# 300w.net
KiCad netlist of a schematic drawn in EasyEDA Pro
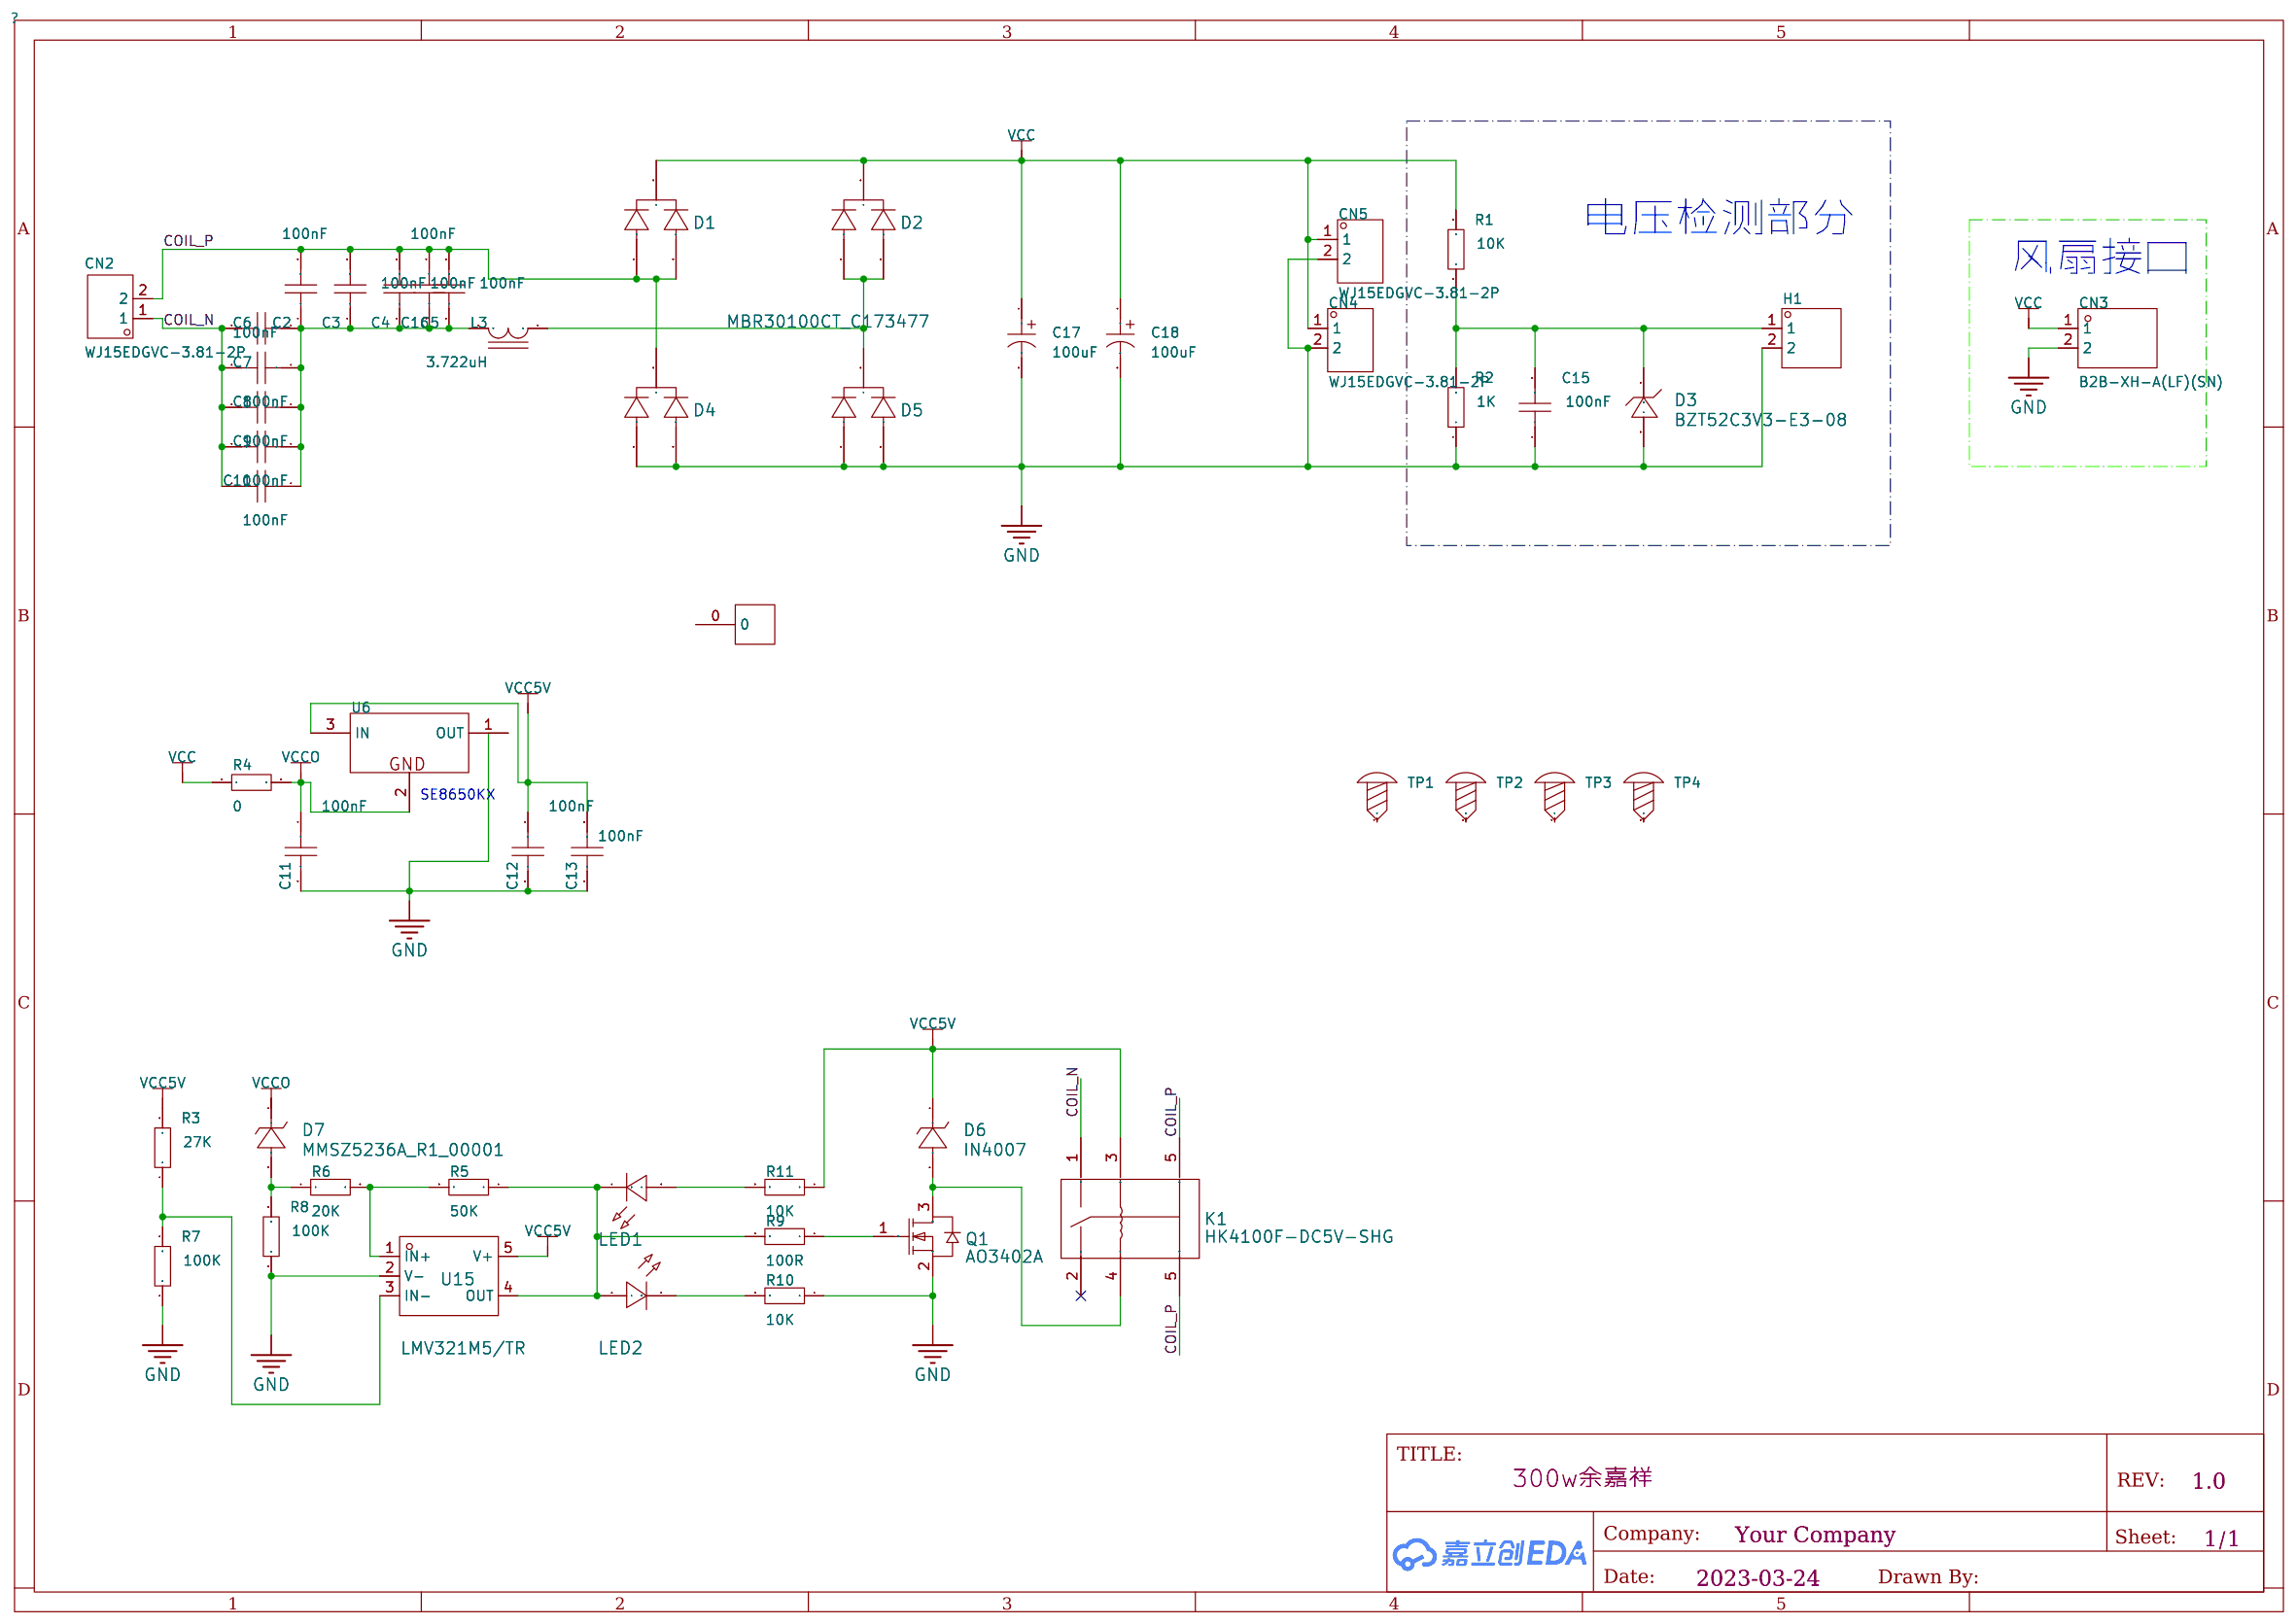
[diagram p0: schematic sheet]

(export (version "E")
  (design (tool "Eeschema 10.0.6"))
  (components
    (comp (ref "C2")
      (value "100nF")
      (footprint "easyedapro:C1206")
      (description "容值:100nF;精度:±10%;额定电压:50V;温度系数:X7R;")
      (libsource (lib "easyedapro") (part "C1210X7R475K630NT"))
    )
    (comp (ref "C3")
      (value "100nF")
      (footprint "easyedapro:C1206")
      (description "容值:100nF;精度:±10%;额定电压:50V;温度系数:X7R;")
      (libsource (lib "easyedapro") (part "C1210X7R475K630NT"))
    )
    (comp (ref "C4")
      (value "100nF")
      (footprint "easyedapro:C1206")
      (description "容值:100nF;精度:±10%;额定电压:50V;温度系数:X7R;")
      (libsource (lib "easyedapro") (part "C1210X7R475K630NT"))
    )
    (comp (ref "C5")
      (value "100nF")
      (footprint "easyedapro:C1206")
      (description "容值:100nF;精度:±10%;额定电压:50V;温度系数:X7R;")
      (libsource (lib "easyedapro") (part "C1210X7R475K630NT"))
    )
    (comp (ref "C6")
      (value "100nF")
      (footprint "easyedapro:C1206")
      (description "容值:100nF;精度:±10%;额定电压:50V;温度系数:X7R;")
      (libsource (lib "easyedapro") (part "C1210X7R475K630NT"))
    )
    (comp (ref "C7")
      (value "100nF")
      (footprint "easyedapro:C1206")
      (description "容值:100nF;精度:±10%;额定电压:50V;温度系数:X7R;")
      (libsource (lib "easyedapro") (part "C1210X7R475K630NT"))
    )
    (comp (ref "C8")
      (value "100nF")
      (footprint "easyedapro:C1206")
      (description "容值:100nF;精度:±10%;额定电压:50V;温度系数:X7R;")
      (libsource (lib "easyedapro") (part "C1210X7R475K630NT"))
    )
    (comp (ref "C9")
      (value "100nF")
      (footprint "easyedapro:C1206")
      (description "容值:100nF;精度:±10%;额定电压:50V;温度系数:X7R;")
      (libsource (lib "easyedapro") (part "C1210X7R475K630NT"))
    )
    (comp (ref "C10")
      (value "100nF")
      (footprint "easyedapro:C1206")
      (description "容值:100nF;精度:±10%;额定电压:50V;温度系数:X7R;")
      (libsource (lib "easyedapro") (part "C1210X7R475K630NT"))
    )
    (comp (ref "C11")
      (value "100nF")
      (footprint "easyedapro:C1206")
      (description "容值:100nF;精度:±10%;额定电压:50V;温度系数:X7R;")
      (libsource (lib "easyedapro") (part "C1210X7R475K630NT"))
    )
    (comp (ref "C12")
      (value "100nF")
      (footprint "easyedapro:C1206")
      (description "容值:100nF;精度:±10%;额定电压:50V;温度系数:X7R;")
      (libsource (lib "easyedapro") (part "C1210X7R475K630NT"))
    )
    (comp (ref "C13")
      (value "100nF")
      (footprint "easyedapro:C1206")
      (description "容值:100nF;精度:±10%;额定电压:50V;温度系数:X7R;")
      (libsource (lib "easyedapro") (part "C1210X7R475K630NT"))
    )
    (comp (ref "C15")
      (value "100nF")
      (footprint "easyedapro:C1206")
      (description "容值:100nF;精度:±10%;额定电压:50V;温度系数:X7R;")
      (libsource (lib "easyedapro") (part "C1210X7R475K630NT"))
    )
    (comp (ref "C16")
      (value "100nF")
      (footprint "easyedapro:C1206")
      (description "容值:100nF;精度:±10%;额定电压:50V;温度系数:X7R;")
      (libsource (lib "easyedapro") (part "C1210X7R475K630NT"))
    )
    (comp (ref "C17")
      (value "100uF")
      (footprint "easyedapro:CAP-TH_BD10.0-P5.00-D0.6-FD")
      (description "类型:-;容值:470uF;精度:±20%;额定电压:35V;纹波电流:-;等效串联电阻:-;")
      (fields
        (field (name "Manufacturer Part") "KNH2470UF35V149EC0017")
        (field (name "Manufacturer") "KNSCHA(科尼盛)")
      )
      (libsource (lib "easyedapro") (part "KNH2470UF35V149EC0017"))
    )
    (comp (ref "C18")
      (value "100uF")
      (footprint "easyedapro:CAP-TH_BD10.0-P5.00-D0.6-FD")
      (description "类型:-;容值:470uF;精度:±20%;额定电压:35V;纹波电流:-;等效串联电阻:-;")
      (fields
        (field (name "Manufacturer Part") "KNH2470UF35V149EC0017")
        (field (name "Manufacturer") "KNSCHA(科尼盛)")
      )
      (libsource (lib "easyedapro") (part "KNH2470UF35V149EC0017"))
    )
    (comp (ref "CN2")
      (value "WJ15EDGVC-3.81-2P")
      (footprint "easyedapro:CONN-TH_WJ15EDGVC-3.81-2P")
      (description "连接器类型:板端/插座-闭口;结构:1x2P;间距:3.81mm;排数:1;每排PIN数:2;安装方式:直针;颜色:绿色;")
      (fields (field (name "Manufacturer") "KANGNEX(康奈克斯电气)"))
      (libsource (lib "easyedapro") (part "WJ15EDGVC-3.81-2P"))
    )
    (comp (ref "CN3")
      (value "B2B-XH-A(LF)(SN)")
      (footprint "easyedapro:CONN-TH_B2B-XH-A-LF-SN")
      (description "参考系列:XH;间距:2.5mm;插针结构:1x2P;排数:1;每排PIN数:2;行距:-;安装方式:-;触头材质:黄铜;")
      (fields (field (name "Manufacturer") "JST"))
      (libsource (lib "easyedapro") (part "B2B-XH-A (LF)(SN)"))
    )
    (comp (ref "CN4")
      (value "WJ15EDGVC-3.81-2P")
      (footprint "easyedapro:CONN-TH_WJ15EDGVC-3.81-2P")
      (description "连接器类型:板端/插座-闭口;结构:1x2P;间距:3.81mm;排数:1;每排PIN数:2;安装方式:直针;颜色:绿色;")
      (fields (field (name "Manufacturer") "KANGNEX(康奈克斯电气)"))
      (libsource (lib "easyedapro") (part "WJ15EDGVC-3.81-2P"))
    )
    (comp (ref "CN5")
      (value "WJ15EDGVC-3.81-2P")
      (footprint "easyedapro:CONN-TH_WJ15EDGVC-3.81-2P")
      (description "连接器类型:板端/插座-闭口;结构:1x2P;间距:3.81mm;排数:1;每排PIN数:2;安装方式:直针;颜色:绿色;")
      (fields (field (name "Manufacturer") "KANGNEX(康奈克斯电气)"))
      (libsource (lib "easyedapro") (part "WJ15EDGVC-3.81-2P"))
    )
    (comp (ref "D1")
      (value "MBR30100CT")
      (footprint "easyedapro:TO-220AB-3_L10.3-W5.0-P2.54-L")
      (fields (field (name "Manufacturer") "MDD"))
      (libsource (lib "easyedapro") (part "MBR30100CT_C173477"))
    )
    (comp (ref "D2")
      (value "MBR30100CT")
      (footprint "easyedapro:TO-220AB-3_L10.3-W5.0-P2.54-L")
      (fields (field (name "Manufacturer") "MDD"))
      (libsource (lib "easyedapro") (part "MBR30100CT_C173477"))
    )
    (comp (ref "D3")
      (value "BZT52C3V3-E3-08")
      (footprint "easyedapro:SOD-123_L2.7-W1.6-LS3.7-RD")
      (fields (field (name "Manufacturer") "VISHAY(威世)"))
      (libsource (lib "easyedapro") (part "BZT52C3V3-E3-08"))
    )
    (comp (ref "D4")
      (value "MBR30100CT_C173477")
      (footprint "easyedapro:TO-220AB-3_L10.3-W5.0-P2.54-L")
      (fields (field (name "Manufacturer Part") "MBR30100CT") (field (name "Manufacturer") "MDD"))
      (libsource (lib "easyedapro") (part "MBR30100CT_C173477"))
    )
    (comp (ref "D5")
      (value "MBR30100CT")
      (footprint "easyedapro:TO-220AB-3_L10.3-W5.0-P2.54-L")
      (fields (field (name "Manufacturer") "MDD"))
      (libsource (lib "easyedapro") (part "MBR30100CT_C173477"))
    )
    (comp (ref "D6")
      (value "IN4007")
      (footprint "easyedapro:SOD-123F_L2.7-W1.6-LS3.8-RD-1")
      (fields
        (field (name "Manufacturer Part") "MMSZ5236A_R1_00001")
        (field (name "Manufacturer") "PANJIT(强茂)")
      )
      (libsource (lib "easyedapro") (part "MMSZ5236A_R1_00001"))
    )
    (comp (ref "D7")
      (value "MMSZ5236A_R1_00001")
      (footprint "easyedapro:SOD-123F_L2.7-W1.6-LS3.8-RD-1")
      (fields (field (name "Manufacturer") "PANJIT(强茂)"))
      (libsource (lib "easyedapro") (part "MMSZ5236A_R1_00001"))
    )
    (comp (ref "H1")
      (value "~")
      (footprint "easyedapro:HDR-TH_2P-P2.54-V-M-1")
      (libsource (lib "easyedapro") (part "210S-1*2P L=11.6MMGold-plated black"))
    )
    (comp (ref "K1")
      (value "HK4100F-DC5V-SHG")
      (footprint "easyedapro:RELAY-TH_HK4100F-DC5V-SHG")
      (fields (field (name "Manufacturer") "汇科"))
      (libsource (lib "easyedapro") (part "HK4100F-DC5V-SHG"))
    )
    (comp (ref "L3")
      (value "3.722uH")
      (footprint "easyedapro:T94/106-LAY")
      (libsource (lib "easyedapro") (part "Ind-Power_2"))
    )
    (comp (ref "LED1")
      (value "~")
      (footprint "easyedapro:LED0805-RD_RED")
      (libsource (lib "easyedapro") (part "LED_R"))
    )
    (comp (ref "LED2")
      (value "~")
      (footprint "easyedapro:LED0805-RD_RED")
      (libsource (lib "easyedapro") (part "LED_R"))
    )
    (comp (ref "Q1")
      (value "AO3402A")
      (footprint "easyedapro:SOT-23-3_L2.9-W1.3-P1.90-LS2.4-BR")
      (fields (field (name "Manufacturer") "UMW(广东友台半导体)"))
      (libsource (lib "easyedapro") (part "AO3402A"))
    )
    (comp (ref "R1") (value "10K") (footprint "easyedapro:R0603") (libsource (lib "easyedapro") (part "电阻")))
    (comp (ref "R2") (value "1K") (footprint "easyedapro:R0603") (libsource (lib "easyedapro") (part "电阻")))
    (comp (ref "R3") (value "27K") (footprint "easyedapro:R0603") (libsource (lib "easyedapro") (part "电阻")))
    (comp (ref "R4") (value "0") (footprint "easyedapro:R0603") (libsource (lib "easyedapro") (part "电阻")))
    (comp (ref "R5") (value "50K") (footprint "easyedapro:R0603") (libsource (lib "easyedapro") (part "电阻")))
    (comp (ref "R6") (value "20K") (footprint "easyedapro:R0603") (libsource (lib "easyedapro") (part "电阻")))
    (comp (ref "R7") (value "100K") (footprint "easyedapro:R0603") (libsource (lib "easyedapro") (part "电阻")))
    (comp (ref "R8") (value "100K") (footprint "easyedapro:R0603") (libsource (lib "easyedapro") (part "电阻")))
    (comp (ref "R9") (value "100R") (footprint "easyedapro:R0603") (libsource (lib "easyedapro") (part "电阻")))
    (comp (ref "R10") (value "10K") (footprint "easyedapro:R0603") (libsource (lib "easyedapro") (part "电阻")))
    (comp (ref "R11") (value "10K") (footprint "easyedapro:R0603") (libsource (lib "easyedapro") (part "电阻")))
    (comp (ref "TP1") (value "~") (footprint "easyedapro:M3螺丝") (libsource (lib "easyedapro") (part "螺丝孔")))
    (comp (ref "TP2") (value "~") (footprint "easyedapro:M3螺丝") (libsource (lib "easyedapro") (part "螺丝孔")))
    (comp (ref "TP3") (value "~") (footprint "easyedapro:M3螺丝") (libsource (lib "easyedapro") (part "螺丝孔")))
    (comp (ref "TP4") (value "~") (footprint "easyedapro:M3螺丝") (libsource (lib "easyedapro") (part "螺丝孔")))
    (comp (ref "U1")
      (value "~")
      (footprint "easyedapro:Cooler-5.5")
      (libsource (lib "easyedapro") (part "fan"))
    )
    (comp (ref "U6")
      (value "UMW78L05")
      (footprint "easyedapro:SOT-89-3_L4.5-W2.5-P1.50-LS4.2-BR")
      (fields (field (name "Manufacturer") "UMW(友台半导体)"))
      (libsource (lib "easyedapro") (part "UMW78L05"))
    )
    (comp (ref "U15")
      (value "LMV321M5/TR")
      (footprint "easyedapro:SOT-23-5_L3.0-W1.7-P0.95-LS2.8-BL")
      (fields (field (name "Manufacturer") "HGC(华冠)"))
      (libsource (lib "easyedapro") (part "LMV321M5/TR"))
    )
  )
  (nets
    (net (code "1") (name "/COIL_N") (class "Default")
      (node (ref "C10") (pin "2") (pinfunction "2_2") (pintype "input"))
      (node (ref "C6") (pin "2") (pinfunction "2_2") (pintype "input"))
      (node (ref "C7") (pin "2") (pinfunction "2_2") (pintype "input"))
      (node (ref "C8") (pin "2") (pinfunction "2_2") (pintype "input"))
      (node (ref "C9") (pin "2") (pinfunction "2_2") (pintype "input"))
      (node (ref "CN2") (pin "1") (pinfunction "1_1") (pintype "input"))
      (node (ref "K1") (pin "1") (pinfunction "1_1") (pintype "input"))
    )
    (net (code "2") (name "/COIL_P") (class "Default")
      (node (ref "C16") (pin "2") (pinfunction "2_2") (pintype "input"))
      (node (ref "C2") (pin "2") (pinfunction "2_2") (pintype "input"))
      (node (ref "C3") (pin "2") (pinfunction "2_2") (pintype "input"))
      (node (ref "C4") (pin "2") (pinfunction "2_2") (pintype "input"))
      (node (ref "C5") (pin "2") (pinfunction "2_2") (pintype "input"))
      (node (ref "CN2") (pin "2") (pinfunction "2_2") (pintype "input"))
      (node (ref "D1") (pin "1") (pinfunction "A1_1") (pintype "input"))
      (node (ref "D1") (pin "3") (pinfunction "A2_3") (pintype "input"))
      (node (ref "D4") (pin "2") (pinfunction "K_2") (pintype "input"))
      (node (ref "K1") (pin "5") (pinfunction "5_5") (pintype "input"))
    )
    (net (code "3") (name "GND") (class "Default")
      (node (ref "C11") (pin "2") (pinfunction "2_2") (pintype "input"))
      (node (ref "C12") (pin "2") (pinfunction "2_2") (pintype "input"))
      (node (ref "C13") (pin "1") (pinfunction "1_1") (pintype "input"))
      (node (ref "C15") (pin "1") (pinfunction "1_1") (pintype "input"))
      (node (ref "C17") (pin "2") (pinfunction "2_2") (pintype "input"))
      (node (ref "C18") (pin "2") (pinfunction "2_2") (pintype "input"))
      (node (ref "CN3") (pin "2") (pinfunction "2_2") (pintype "input"))
      (node (ref "CN4") (pin "2") (pinfunction "2_2") (pintype "input"))
      (node (ref "CN5") (pin "2") (pinfunction "2_2") (pintype "input"))
      (node (ref "D3") (pin "2") (pinfunction "A_2") (pintype "input"))
      (node (ref "D4") (pin "1") (pinfunction "A1_1") (pintype "input"))
      (node (ref "D4") (pin "3") (pinfunction "A2_3") (pintype "input"))
      (node (ref "D5") (pin "1") (pinfunction "A1_1") (pintype "input"))
      (node (ref "D5") (pin "3") (pinfunction "A2_3") (pintype "input"))
      (node (ref "H1") (pin "2") (pinfunction "2_2") (pintype "input"))
      (node (ref "Q1") (pin "2") (pinfunction "S_2") (pintype "input"))
      (node (ref "R10") (pin "1") (pinfunction "1_1") (pintype "input"))
      (node (ref "R2") (pin "1") (pinfunction "1_1") (pintype "input"))
      (node (ref "R7") (pin "1") (pinfunction "1_1") (pintype "input"))
      (node (ref "R8") (pin "1") (pinfunction "1_1") (pintype "input"))
      (node (ref "U15") (pin "2") (pinfunction "V-_2") (pintype "input"))
      (node (ref "U6") (pin "1") (pinfunction "OUT_1") (pintype "input"))
    )
    (net (code "4") (name "Net-(C10-Pad1)") (class "Default")
      (node (ref "C10") (pin "1") (pinfunction "1_1") (pintype "input"))
      (node (ref "C16") (pin "1") (pinfunction "1_1") (pintype "input"))
      (node (ref "C2") (pin "1") (pinfunction "1_1") (pintype "input"))
      (node (ref "C3") (pin "1") (pinfunction "1_1") (pintype "input"))
      (node (ref "C4") (pin "1") (pinfunction "1_1") (pintype "input"))
      (node (ref "C5") (pin "1") (pinfunction "1_1") (pintype "input"))
      (node (ref "C6") (pin "1") (pinfunction "1_1") (pintype "input"))
      (node (ref "C7") (pin "1") (pinfunction "1_1") (pintype "input"))
      (node (ref "C8") (pin "1") (pinfunction "1_1") (pintype "input"))
      (node (ref "C9") (pin "1") (pinfunction "1_1") (pintype "input"))
      (node (ref "L3") (pin "2") (pinfunction "2_2") (pintype "input"))
    )
    (net (code "5") (name "Net-(D2-A1)") (class "Default")
      (node (ref "D2") (pin "1") (pinfunction "A1_1") (pintype "input"))
      (node (ref "D2") (pin "3") (pinfunction "A2_3") (pintype "input"))
      (node (ref "D5") (pin "2") (pinfunction "K_2") (pintype "input"))
      (node (ref "L3") (pin "1") (pinfunction "1_1") (pintype "input"))
    )
    (net (code "6") (name "Net-(D3-C)") (class "Default")
      (node (ref "C15") (pin "2") (pinfunction "2_2") (pintype "input"))
      (node (ref "D3") (pin "1") (pinfunction "C_1") (pintype "input"))
      (node (ref "H1") (pin "1") (pinfunction "1_1") (pintype "input"))
      (node (ref "R1") (pin "1") (pinfunction "1_1") (pintype "input"))
      (node (ref "R2") (pin "2") (pinfunction "2_2") (pintype "input"))
    )
    (net (code "7") (name "Net-(D6-A)") (class "Default")
      (node (ref "D6") (pin "2") (pinfunction "A_2") (pintype "input"))
      (node (ref "K1") (pin "4") (pinfunction "4_4") (pintype "input"))
      (node (ref "Q1") (pin "3") (pinfunction "D_3") (pintype "input"))
    )
    (net (code "8") (name "Net-(D7-A)") (class "Default")
      (node (ref "D7") (pin "2") (pinfunction "A_2") (pintype "input"))
      (node (ref "R6") (pin "1") (pinfunction "1_1") (pintype "input"))
      (node (ref "R8") (pin "2") (pinfunction "2_2") (pintype "input"))
    )
    (net (code "9") (name "Net-(LED1-A)") (class "Default")
      (node (ref "LED1") (pin "2") (pinfunction "A_2") (pintype "input"))
      (node (ref "R11") (pin "2") (pinfunction "2_2") (pintype "input"))
    )
    (net (code "10") (name "Net-(LED1-C)") (class "Default")
      (node (ref "LED1") (pin "1") (pinfunction "C_1") (pintype "input"))
      (node (ref "LED2") (pin "2") (pinfunction "A_2") (pintype "input"))
      (node (ref "R5") (pin "1") (pinfunction "1_1") (pintype "input"))
      (node (ref "R9") (pin "2") (pinfunction "2_2") (pintype "input"))
      (node (ref "U15") (pin "4") (pinfunction "OUT_4") (pintype "input"))
    )
    (net (code "11") (name "Net-(LED2-C)") (class "Default")
      (node (ref "LED2") (pin "1") (pinfunction "C_1") (pintype "input"))
      (node (ref "R10") (pin "2") (pinfunction "2_2") (pintype "input"))
    )
    (net (code "12") (name "Net-(Q1-G)") (class "Default")
      (node (ref "Q1") (pin "1") (pinfunction "G_1") (pintype "input"))
      (node (ref "R9") (pin "1") (pinfunction "1_1") (pintype "input"))
    )
    (net (code "13") (name "Net-(U15-IN+)") (class "Default")
      (node (ref "R5") (pin "2") (pinfunction "2_2") (pintype "input"))
      (node (ref "R6") (pin "2") (pinfunction "2_2") (pintype "input"))
      (node (ref "U15") (pin "1") (pinfunction "IN+_1") (pintype "input"))
    )
    (net (code "14") (name "Net-(U15-IN-)") (class "Default")
      (node (ref "R3") (pin "1") (pinfunction "1_1") (pintype "input"))
      (node (ref "R7") (pin "2") (pinfunction "2_2") (pintype "input"))
      (node (ref "U15") (pin "3") (pinfunction "IN-_3") (pintype "input"))
    )
    (net (code "15") (name "VCC") (class "Default")
      (node (ref "C17") (pin "1") (pinfunction "1_1") (pintype "input"))
      (node (ref "C18") (pin "1") (pinfunction "1_1") (pintype "input"))
      (node (ref "CN3") (pin "1") (pinfunction "1_1") (pintype "input"))
      (node (ref "CN4") (pin "1") (pinfunction "1_1") (pintype "input"))
      (node (ref "CN5") (pin "1") (pinfunction "1_1") (pintype "input"))
      (node (ref "D1") (pin "2") (pinfunction "K_2") (pintype "input"))
      (node (ref "D2") (pin "2") (pinfunction "K_2") (pintype "input"))
      (node (ref "R1") (pin "2") (pinfunction "2_2") (pintype "input"))
      (node (ref "R4") (pin "1") (pinfunction "1_1") (pintype "input"))
    )
    (net (code "16") (name "VCC5V") (class "Default")
      (node (ref "C12") (pin "1") (pinfunction "1_1") (pintype "input"))
      (node (ref "C13") (pin "2") (pinfunction "2_2") (pintype "input"))
      (node (ref "D6") (pin "1") (pinfunction "K_1") (pintype "input"))
      (node (ref "K1") (pin "3") (pinfunction "3_3") (pintype "input"))
      (node (ref "R11") (pin "1") (pinfunction "1_1") (pintype "input"))
      (node (ref "R3") (pin "2") (pinfunction "2_2") (pintype "input"))
      (node (ref "U15") (pin "5") (pinfunction "V+_5") (pintype "input"))
      (node (ref "U6") (pin "3") (pinfunction "IN_3") (pintype "input"))
    )
    (net (code "17") (name "VCCO") (class "Default")
      (node (ref "C11") (pin "1") (pinfunction "1_1") (pintype "input"))
      (node (ref "D7") (pin "1") (pinfunction "K_1") (pintype "input"))
      (node (ref "R4") (pin "2") (pinfunction "2_2") (pintype "input"))
      (node (ref "U6") (pin "2") (pinfunction "GND_2") (pintype "input"))
    )
    (net (code "18") (name "unconnected-(K1-Pad2)") (class "Default")
      (node (ref "K1") (pin "2") (pinfunction "2_2") (pintype "input+no_connect"))
    )
    (net (code "19") (name "unconnected-(TP1-Pad1)") (class "Default")
      (node (ref "TP1") (pin "1") (pinfunction "1_1") (pintype "input"))
    )
    (net (code "20") (name "unconnected-(TP2-Pad1)") (class "Default")
      (node (ref "TP2") (pin "1") (pinfunction "1_1") (pintype "input"))
    )
    (net (code "21") (name "unconnected-(TP3-Pad1)") (class "Default")
      (node (ref "TP3") (pin "1") (pinfunction "1_1") (pintype "input"))
    )
    (net (code "22") (name "unconnected-(TP4-Pad1)") (class "Default")
      (node (ref "TP4") (pin "1") (pinfunction "1_1") (pintype "input"))
    )
    (net (code "23") (name "unconnected-(U1-Pad0)") (class "Default")
      (node (ref "U1") (pin "0") (pinfunction "0_0") (pintype "input"))
    )
  )
)
